# femto.net
KiCad netlist of a schematic drawn in EAGLE
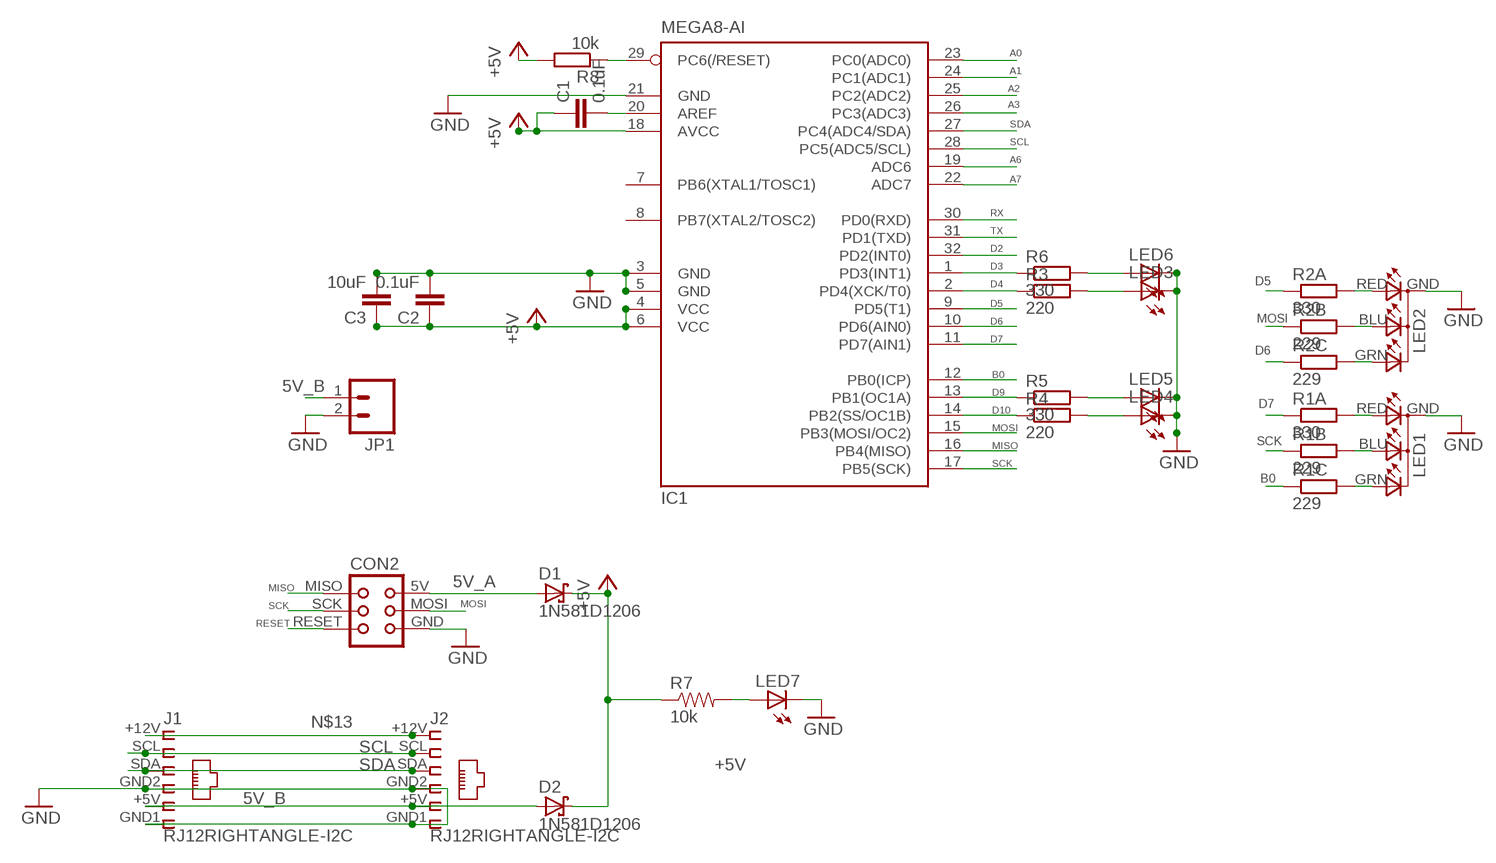
[diagram p0: schematic, sheet 1]

(export (version "E")
  (design (tool "Eeschema 10.0.6"))
  (components
    (comp (ref "C1")
      (value "0.1uF")
      (footprint "eagle-import:C1206")
      (libsource (lib "eagle-import") (part "C-EUC1206"))
    )
    (comp (ref "C2")
      (value "0.1uF")
      (footprint "eagle-import:C1206")
      (libsource (lib "eagle-import") (part "C-EUC1206"))
    )
    (comp (ref "C3")
      (value "10uF")
      (footprint "eagle-import:C1206")
      (libsource (lib "eagle-import") (part "C-EUC1206"))
    )
    (comp (ref "CON2")
      (value "TINYISPTAG")
      (footprint "eagle-import:TC2030-MCP")
      (libsource (lib "eagle-import") (part "TINYISPTAG"))
    )
    (comp (ref "D1")
      (value "1N581D1206")
      (footprint "eagle-import:LED-1206")
      (libsource (lib "eagle-import") (part "1N581D1206"))
    )
    (comp (ref "D2")
      (value "1N581D1206")
      (footprint "eagle-import:LED-1206")
      (libsource (lib "eagle-import") (part "1N581D1206"))
    )
    (comp (ref "IC1")
      (value "MEGA8-AI")
      (footprint "eagle-import:TQFP32-08")
      (fields (field (name "MPN") "ATMEGA8-16AU"))
      (libsource (lib "eagle-import") (part "MEGA8-AI"))
    )
    (comp (ref "J1")
      (value "RJ12RIGHTANGLE-I2C")
      (footprint "eagle-import:RJ12-RIGHTANGLE-I2C")
      (libsource (lib "eagle-import") (part "RJ12RIGHTANGLE-I2C"))
    )
    (comp (ref "J2")
      (value "RJ12RIGHTANGLE-I2C")
      (footprint "eagle-import:RJ12-RIGHTANGLE-I2C")
      (libsource (lib "eagle-import") (part "RJ12RIGHTANGLE-I2C"))
    )
    (comp (ref "JP1")
      (value "M023.5MM")
      (footprint "eagle-import:SCREWTERMINAL-3.5MM-2")
      (libsource (lib "eagle-import") (part "M023.5MM"))
    )
    (comp (ref "LED1")
      (value "RGB-COMMON-CATHODE")
      (footprint "eagle-import:LED-TRICOLOR-THROUGHHOLE")
      (libsource (lib "eagle-import") (part "RGB-COMMON-CATHODE"))
    )
    (comp (ref "LED2")
      (value "RGB-COMMON-CATHODE")
      (footprint "eagle-import:LED-TRICOLOR-THROUGHHOLE")
      (libsource (lib "eagle-import") (part "RGB-COMMON-CATHODE"))
    )
    (comp (ref "LED3")
      (value "LED3MM")
      (footprint "eagle-import:LED3MM")
      (libsource (lib "eagle-import") (part "lpatiny_LED3MM"))
    )
    (comp (ref "LED4")
      (value "LED3MM")
      (footprint "eagle-import:LED3MM")
      (libsource (lib "eagle-import") (part "lpatiny_LED3MM"))
    )
    (comp (ref "LED5")
      (value "LED3MM")
      (footprint "eagle-import:LED3MM")
      (libsource (lib "eagle-import") (part "lpatiny_LED3MM"))
    )
    (comp (ref "LED6")
      (value "LED3MM")
      (footprint "eagle-import:LED3MM")
      (libsource (lib "eagle-import") (part "lpatiny_LED3MM"))
    )
    (comp (ref "LED7")
      (value "LEDCHIP-LED0603")
      (footprint "eagle-import:CHIP-LED0603")
      (libsource (lib "eagle-import") (part "LEDCHIP-LED0603"))
    )
    (comp (ref "R1A")
      (value "330")
      (footprint "eagle-import:M1206")
      (libsource (lib "eagle-import") (part "R-EU_M1206"))
    )
    (comp (ref "R1B")
      (value "229")
      (footprint "eagle-import:M1206")
      (libsource (lib "eagle-import") (part "R-EU_M1206"))
    )
    (comp (ref "R1C")
      (value "229")
      (footprint "eagle-import:M1206")
      (libsource (lib "eagle-import") (part "R-EU_M1206"))
    )
    (comp (ref "R2A")
      (value "330")
      (footprint "eagle-import:M1206")
      (libsource (lib "eagle-import") (part "R-EU_M1206"))
    )
    (comp (ref "R2B")
      (value "229")
      (footprint "eagle-import:M1206")
      (libsource (lib "eagle-import") (part "R-EU_M1206"))
    )
    (comp (ref "R2C")
      (value "229")
      (footprint "eagle-import:M1206")
      (libsource (lib "eagle-import") (part "R-EU_M1206"))
    )
    (comp (ref "R3")
      (value "220")
      (footprint "eagle-import:M1206")
      (libsource (lib "eagle-import") (part "R-EU_M1206"))
    )
    (comp (ref "R4")
      (value "220")
      (footprint "eagle-import:M1206")
      (libsource (lib "eagle-import") (part "R-EU_M1206"))
    )
    (comp (ref "R5")
      (value "330")
      (footprint "eagle-import:M1206")
      (libsource (lib "eagle-import") (part "R-EU_M1206"))
    )
    (comp (ref "R6")
      (value "330")
      (footprint "eagle-import:M1206")
      (libsource (lib "eagle-import") (part "R-EU_M1206"))
    )
    (comp (ref "R7")
      (value "10k")
      (footprint "eagle-import:0603-RES")
      (libsource (lib "eagle-import") (part "RESISTOR0603-RES"))
    )
    (comp (ref "R8")
      (value "10k")
      (footprint "eagle-import:M1206")
      (libsource (lib "eagle-import") (part "R-EU_M1206"))
    )
  )
  (nets
    (net (code "1") (name "+5V") (class "Default")
      (node (ref "C1") (pin "1") (pinfunction "1_1") (pintype "passive"))
      (node (ref "C2") (pin "1") (pinfunction "1_1") (pintype "passive"))
      (node (ref "C3") (pin "1") (pinfunction "1_1") (pintype "passive"))
      (node (ref "D1") (pin "C") (pinfunction "C_C") (pintype "passive"))
      (node (ref "D2") (pin "C") (pinfunction "C_C") (pintype "passive"))
      (node (ref "IC1") (pin "18") (pinfunction "AVCC_18") (pintype "power_in"))
      (node (ref "IC1") (pin "4") (pinfunction "VCC_4") (pintype "power_in"))
      (node (ref "IC1") (pin "6") (pinfunction "VCC_6") (pintype "power_in"))
      (node (ref "R7") (pin "1") (pinfunction "1_1") (pintype "passive"))
      (node (ref "R8") (pin "2") (pinfunction "2_2") (pintype "passive"))
    )
    (net (code "2") (name "/5V_A") (class "Default")
      (node (ref "CON2") (pin "5V") (pinfunction "VCC_5V") (pintype "passive"))
      (node (ref "D1") (pin "A") (pinfunction "A_A") (pintype "passive"))
    )
    (net (code "3") (name "/5V_B") (class "Default")
      (node (ref "D2") (pin "A") (pinfunction "A_A") (pintype "passive"))
      (node (ref "J1") (pin "+5V") (pinfunction "5_+5V") (pintype "bidirectional"))
      (node (ref "J2") (pin "+5V") (pinfunction "5_+5V") (pintype "bidirectional"))
      (node (ref "JP1") (pin "1") (pinfunction "1_1") (pintype "passive"))
    )
    (net (code "4") (name "/A0") (class "Default")
      (node (ref "IC1") (pin "23") (pinfunction "PC0(ADC0)_23") (pintype "bidirectional"))
    )
    (net (code "5") (name "/A1") (class "Default")
      (node (ref "IC1") (pin "24") (pinfunction "PC1(ADC1)_24") (pintype "bidirectional"))
    )
    (net (code "6") (name "/A2") (class "Default")
      (node (ref "IC1") (pin "25") (pinfunction "PC2(ADC2)_25") (pintype "bidirectional"))
    )
    (net (code "7") (name "/A3") (class "Default")
      (node (ref "IC1") (pin "26") (pinfunction "PC3(ADC3)_26") (pintype "bidirectional"))
    )
    (net (code "8") (name "/A6") (class "Default")
      (node (ref "IC1") (pin "19") (pinfunction "ADC6_19") (pintype "bidirectional"))
    )
    (net (code "9") (name "/A7") (class "Default")
      (node (ref "IC1") (pin "22") (pinfunction "ADC7_22") (pintype "bidirectional"))
    )
    (net (code "10") (name "/B0") (class "Default")
      (node (ref "IC1") (pin "12") (pinfunction "PB0(ICP)_12") (pintype "bidirectional"))
      (node (ref "R1C") (pin "1") (pinfunction "1_1") (pintype "passive"))
    )
    (net (code "11") (name "/D2") (class "Default")
      (node (ref "IC1") (pin "32") (pinfunction "PD2(INT0)_32") (pintype "bidirectional"))
    )
    (net (code "12") (name "/D3") (class "Default")
      (node (ref "IC1") (pin "1") (pinfunction "PD3(INT1)_1") (pintype "bidirectional"))
      (node (ref "R6") (pin "1") (pinfunction "1_1") (pintype "passive"))
    )
    (net (code "13") (name "/D4") (class "Default")
      (node (ref "IC1") (pin "2") (pinfunction "PD4(XCK/T0)_2") (pintype "bidirectional"))
      (node (ref "R3") (pin "1") (pinfunction "1_1") (pintype "passive"))
    )
    (net (code "14") (name "/D5") (class "Default")
      (node (ref "IC1") (pin "9") (pinfunction "PD5(T1)_9") (pintype "bidirectional"))
      (node (ref "R2A") (pin "1") (pinfunction "1_1") (pintype "passive"))
    )
    (net (code "15") (name "/D6") (class "Default")
      (node (ref "IC1") (pin "10") (pinfunction "PD6(AIN0)_10") (pintype "bidirectional"))
      (node (ref "R2C") (pin "1") (pinfunction "1_1") (pintype "passive"))
    )
    (net (code "16") (name "/D7") (class "Default")
      (node (ref "IC1") (pin "11") (pinfunction "PD7(AIN1)_11") (pintype "bidirectional"))
      (node (ref "R1A") (pin "1") (pinfunction "1_1") (pintype "passive"))
    )
    (net (code "17") (name "/D9") (class "Default")
      (node (ref "IC1") (pin "13") (pinfunction "PB1(OC1A)_13") (pintype "bidirectional"))
      (node (ref "R5") (pin "1") (pinfunction "1_1") (pintype "passive"))
    )
    (net (code "18") (name "/D10") (class "Default")
      (node (ref "IC1") (pin "14") (pinfunction "PB2(SS/OC1B)_14") (pintype "bidirectional"))
      (node (ref "R4") (pin "1") (pinfunction "1_1") (pintype "passive"))
    )
    (net (code "19") (name "/MISO") (class "Default")
      (node (ref "CON2") (pin "MISO") (pinfunction "MISO_MISO") (pintype "passive"))
      (node (ref "IC1") (pin "16") (pinfunction "PB4(MISO)_16") (pintype "bidirectional"))
    )
    (net (code "20") (name "/MOSI") (class "Default")
      (node (ref "CON2") (pin "MOSI") (pinfunction "MOSI_MOSI") (pintype "passive"))
      (node (ref "IC1") (pin "15") (pinfunction "PB3(MOSI/OC2)_15") (pintype "bidirectional"))
      (node (ref "R2B") (pin "1") (pinfunction "1_1") (pintype "passive"))
    )
    (net (code "21") (name "/N$13") (class "Default")
      (node (ref "J1") (pin "+12V") (pinfunction "1_+12V") (pintype "bidirectional"))
      (node (ref "J2") (pin "+12V") (pinfunction "1_+12V") (pintype "bidirectional"))
    )
    (net (code "22") (name "/RESET") (class "Default")
      (node (ref "CON2") (pin "RESET") (pinfunction "RESET_RESET") (pintype "passive"))
      (node (ref "IC1") (pin "29") (pinfunction "PC6(/RESET)_29") (pintype "bidirectional"))
      (node (ref "R8") (pin "1") (pinfunction "1_1") (pintype "passive"))
    )
    (net (code "23") (name "/RX") (class "Default")
      (node (ref "IC1") (pin "30") (pinfunction "PD0(RXD)_30") (pintype "bidirectional"))
    )
    (net (code "24") (name "/SCK") (class "Default")
      (node (ref "CON2") (pin "SCK") (pinfunction "SCK_SCK") (pintype "passive"))
      (node (ref "IC1") (pin "17") (pinfunction "PB5(SCK)_17") (pintype "bidirectional"))
      (node (ref "R1B") (pin "1") (pinfunction "1_1") (pintype "passive"))
    )
    (net (code "25") (name "/SCL") (class "Default")
      (node (ref "IC1") (pin "28") (pinfunction "PC5(ADC5/SCL)_28") (pintype "bidirectional"))
      (node (ref "J1") (pin "SCL") (pinfunction "2_SCL") (pintype "bidirectional"))
      (node (ref "J2") (pin "SCL") (pinfunction "2_SCL") (pintype "bidirectional"))
    )
    (net (code "26") (name "/SDA") (class "Default")
      (node (ref "IC1") (pin "27") (pinfunction "PC4(ADC4/SDA)_27") (pintype "bidirectional"))
      (node (ref "J1") (pin "SDA") (pinfunction "3_SDA") (pintype "bidirectional"))
      (node (ref "J2") (pin "SDA") (pinfunction "3_SDA") (pintype "bidirectional"))
    )
    (net (code "27") (name "/TX") (class "Default")
      (node (ref "IC1") (pin "31") (pinfunction "PD1(TXD)_31") (pintype "bidirectional"))
    )
    (net (code "28") (name "GND") (class "Default")
      (node (ref "C2") (pin "2") (pinfunction "2_2") (pintype "passive"))
      (node (ref "C3") (pin "2") (pinfunction "2_2") (pintype "passive"))
      (node (ref "CON2") (pin "GND") (pinfunction "GND_GND") (pintype "passive"))
      (node (ref "IC1") (pin "21") (pinfunction "GND_21") (pintype "power_in"))
      (node (ref "IC1") (pin "3") (pinfunction "GND_3") (pintype "power_in"))
      (node (ref "IC1") (pin "5") (pinfunction "GND_5") (pintype "power_in"))
      (node (ref "J1") (pin "GND1") (pinfunction "6_GND1") (pintype "bidirectional"))
      (node (ref "J1") (pin "GND2") (pinfunction "4_GND2") (pintype "bidirectional"))
      (node (ref "J2") (pin "GND1") (pinfunction "6_GND1") (pintype "bidirectional"))
      (node (ref "J2") (pin "GND2") (pinfunction "4_GND2") (pintype "bidirectional"))
      (node (ref "JP1") (pin "2") (pinfunction "2_2") (pintype "passive"))
      (node (ref "LED1") (pin "GND") (pinfunction "A2_GND") (pintype "passive"))
      (node (ref "LED2") (pin "GND") (pinfunction "A2_GND") (pintype "passive"))
      (node (ref "LED3") (pin "K") (pinfunction "C_K") (pintype "passive"))
      (node (ref "LED4") (pin "K") (pinfunction "C_K") (pintype "passive"))
      (node (ref "LED5") (pin "K") (pinfunction "C_K") (pintype "passive"))
      (node (ref "LED6") (pin "K") (pinfunction "C_K") (pintype "passive"))
      (node (ref "LED7") (pin "C") (pinfunction "C_C") (pintype "passive"))
    )
    (net (code "29") (name "Net-(IC1-AREF)") (class "Default")
      (node (ref "C1") (pin "2") (pinfunction "2_2") (pintype "passive"))
      (node (ref "IC1") (pin "20") (pinfunction "AREF_20") (pintype "passive"))
    )
    (net (code "30") (name "Net-(LED1-CBLUE)") (class "Default")
      (node (ref "LED1") (pin "BLU") (pinfunction "CBLUE_BLU") (pintype "passive"))
      (node (ref "R1B") (pin "2") (pinfunction "2_2") (pintype "passive"))
    )
    (net (code "31") (name "Net-(LED1-CGREEN)") (class "Default")
      (node (ref "LED1") (pin "GRN") (pinfunction "CGREEN_GRN") (pintype "passive"))
      (node (ref "R1C") (pin "2") (pinfunction "2_2") (pintype "passive"))
    )
    (net (code "32") (name "Net-(LED1-CRED)") (class "Default")
      (node (ref "LED1") (pin "RED") (pinfunction "CRED_RED") (pintype "passive"))
      (node (ref "R1A") (pin "2") (pinfunction "2_2") (pintype "passive"))
    )
    (net (code "33") (name "Net-(LED2-CBLUE)") (class "Default")
      (node (ref "LED2") (pin "BLU") (pinfunction "CBLUE_BLU") (pintype "passive"))
      (node (ref "R2B") (pin "2") (pinfunction "2_2") (pintype "passive"))
    )
    (net (code "34") (name "Net-(LED2-CGREEN)") (class "Default")
      (node (ref "LED2") (pin "GRN") (pinfunction "CGREEN_GRN") (pintype "passive"))
      (node (ref "R2C") (pin "2") (pinfunction "2_2") (pintype "passive"))
    )
    (net (code "35") (name "Net-(LED2-CRED)") (class "Default")
      (node (ref "LED2") (pin "RED") (pinfunction "CRED_RED") (pintype "passive"))
      (node (ref "R2A") (pin "2") (pinfunction "2_2") (pintype "passive"))
    )
    (net (code "36") (name "Net-(LED3-PadA)") (class "Default")
      (node (ref "LED3") (pin "A") (pinfunction "A_A") (pintype "passive"))
      (node (ref "R3") (pin "2") (pinfunction "2_2") (pintype "passive"))
    )
    (net (code "37") (name "Net-(LED4-PadA)") (class "Default")
      (node (ref "LED4") (pin "A") (pinfunction "A_A") (pintype "passive"))
      (node (ref "R4") (pin "2") (pinfunction "2_2") (pintype "passive"))
    )
    (net (code "38") (name "Net-(LED5-PadA)") (class "Default")
      (node (ref "LED5") (pin "A") (pinfunction "A_A") (pintype "passive"))
      (node (ref "R5") (pin "2") (pinfunction "2_2") (pintype "passive"))
    )
    (net (code "39") (name "Net-(LED6-PadA)") (class "Default")
      (node (ref "LED6") (pin "A") (pinfunction "A_A") (pintype "passive"))
      (node (ref "R6") (pin "2") (pinfunction "2_2") (pintype "passive"))
    )
    (net (code "40") (name "Net-(LED7-PadA)") (class "Default")
      (node (ref "LED7") (pin "A") (pinfunction "A_A") (pintype "passive"))
      (node (ref "R7") (pin "2") (pinfunction "2_2") (pintype "passive"))
    )
    (net (code "41") (name "unconnected-(IC1-PB6(XTAL1{slash}TOSC1)-Pad7)") (class "Default")
      (node (ref "IC1") (pin "7") (pinfunction "PB6(XTAL1/TOSC1)_7") (pintype "bidirectional"))
    )
    (net (code "42") (name "unconnected-(IC1-PB7(XTAL2{slash}TOSC2)-Pad8)") (class "Default")
      (node (ref "IC1") (pin "8") (pinfunction "PB7(XTAL2/TOSC2)_8") (pintype "bidirectional"))
    )
  )
)
